# LCD_ControlRev1Fix1.net
KiCad netlist of a schematic drawn in EAGLE
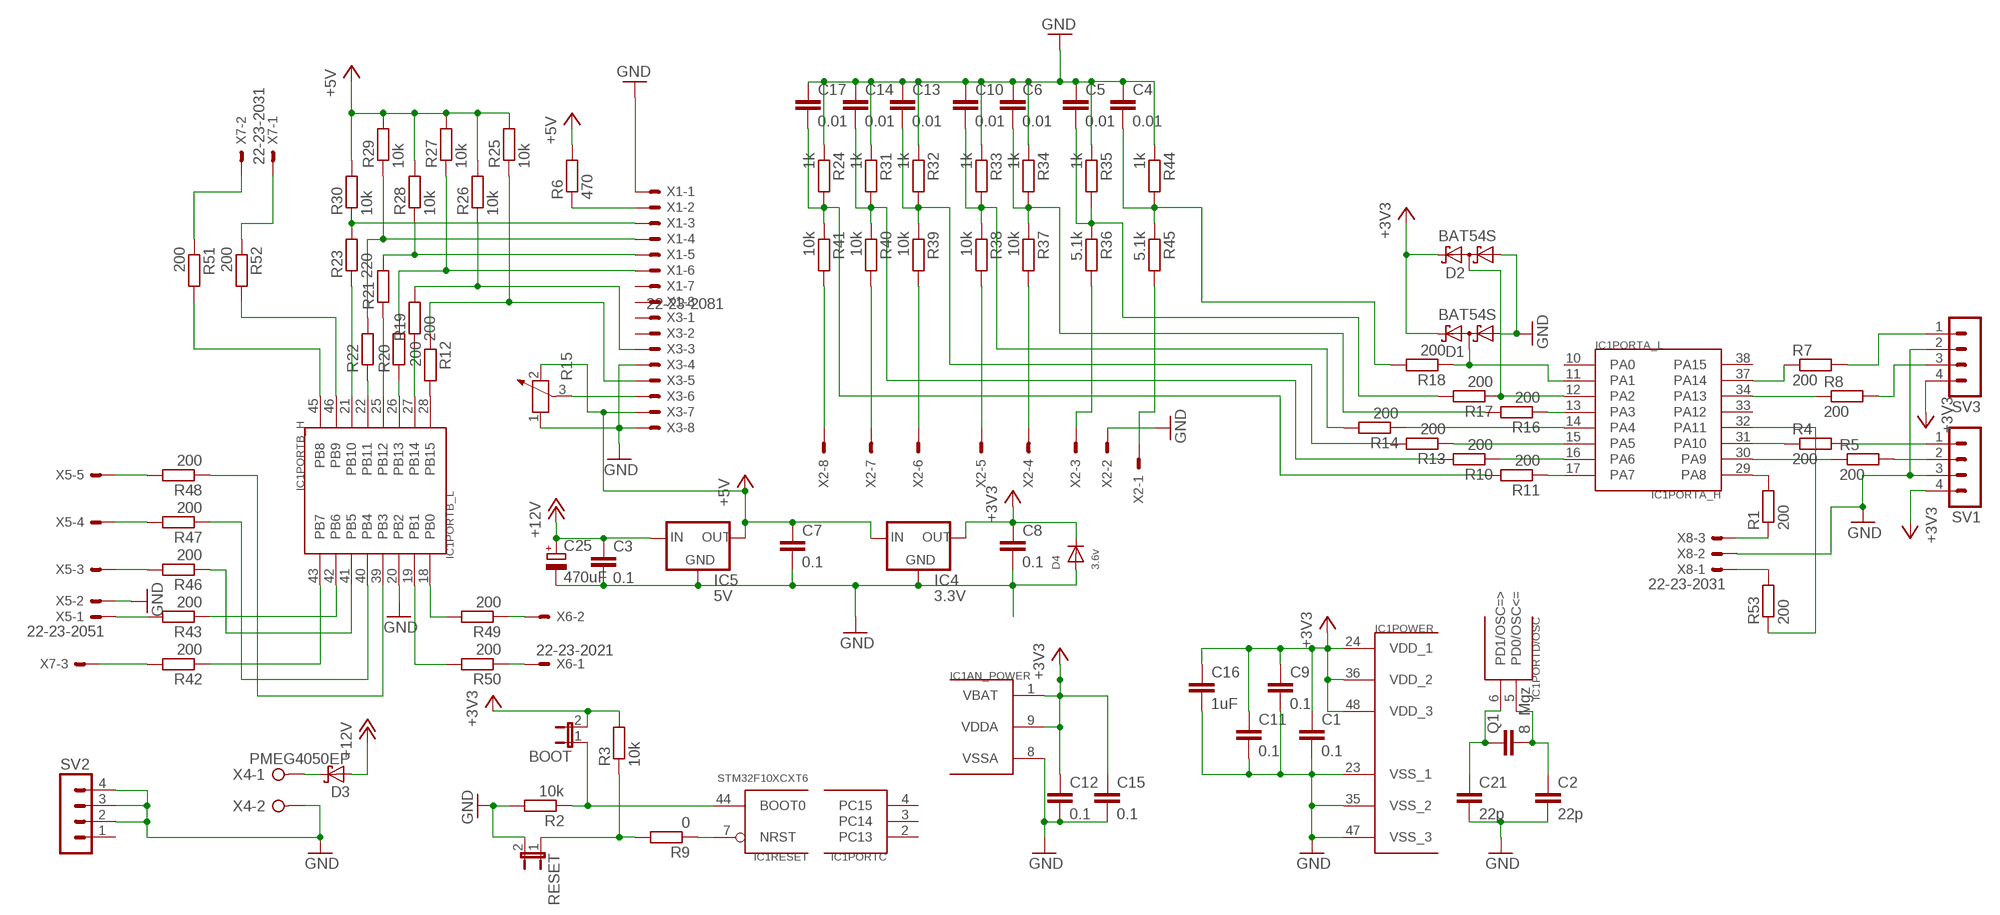
[diagram p0: schematic, sheet 1]

(export (version "E")
  (design (tool "Eeschema 10.0.6"))
  (components
    (comp (ref "BOOT")
      (value "JP1E")
      (footprint "eagle-import:JP1")
      (libsource (lib "eagle-import") (part "JP1E"))
    )
    (comp (ref "C1")
      (value "0.1")
      (footprint "eagle-import:C0402")
      (libsource (lib "eagle-import") (part "C-EUC0402"))
    )
    (comp (ref "C2")
      (value "22p")
      (footprint "eagle-import:C0603")
      (libsource (lib "eagle-import") (part "C-EUC0603"))
    )
    (comp (ref "C3")
      (value "0.1")
      (footprint "eagle-import:C1206")
      (libsource (lib "eagle-import") (part "C-EUC1206"))
    )
    (comp (ref "C4")
      (value "0.01")
      (footprint "eagle-import:C0603")
      (libsource (lib "eagle-import") (part "rcl_334_C-EUC0603"))
    )
    (comp (ref "C5")
      (value "0.01")
      (footprint "eagle-import:C0603")
      (libsource (lib "eagle-import") (part "rcl_334_C-EUC0603"))
    )
    (comp (ref "C6")
      (value "0.01")
      (footprint "eagle-import:C0603")
      (libsource (lib "eagle-import") (part "rcl_334_C-EUC0603"))
    )
    (comp (ref "C7")
      (value "0.1")
      (footprint "eagle-import:C1206")
      (libsource (lib "eagle-import") (part "C-EUC1206"))
    )
    (comp (ref "C8")
      (value "0.1")
      (footprint "eagle-import:C1206")
      (libsource (lib "eagle-import") (part "C-EUC1206"))
    )
    (comp (ref "C9")
      (value "0.1")
      (footprint "eagle-import:C0402")
      (libsource (lib "eagle-import") (part "C-EUC0402"))
    )
    (comp (ref "C10")
      (value "0.01")
      (footprint "eagle-import:C0603")
      (libsource (lib "eagle-import") (part "rcl_334_C-EUC0603"))
    )
    (comp (ref "C11")
      (value "0.1")
      (footprint "eagle-import:C0402")
      (libsource (lib "eagle-import") (part "C-EUC0402"))
    )
    (comp (ref "C12")
      (value "0.1")
      (footprint "eagle-import:C0402")
      (libsource (lib "eagle-import") (part "C-EUC0402"))
    )
    (comp (ref "C13")
      (value "0.01")
      (footprint "eagle-import:C0603")
      (libsource (lib "eagle-import") (part "rcl_334_C-EUC0603"))
    )
    (comp (ref "C14")
      (value "0.01")
      (footprint "eagle-import:C0603")
      (libsource (lib "eagle-import") (part "rcl_334_C-EUC0603"))
    )
    (comp (ref "C15")
      (value "0.1")
      (footprint "eagle-import:C0402")
      (libsource (lib "eagle-import") (part "C-EUC0402"))
    )
    (comp (ref "C16")
      (value "1uF")
      (footprint "eagle-import:C0603")
      (libsource (lib "eagle-import") (part "C-EUC0603"))
    )
    (comp (ref "C17")
      (value "0.01")
      (footprint "eagle-import:C0603")
      (libsource (lib "eagle-import") (part "rcl_334_C-EUC0603"))
    )
    (comp (ref "C21")
      (value "22p")
      (footprint "eagle-import:C0603")
      (libsource (lib "eagle-import") (part "C-EUC0603"))
    )
    (comp (ref "C25")
      (value "470uF")
      (footprint "eagle-import:E5-10,5")
      (libsource (lib "eagle-import") (part "CPOL-EUE5-10.5"))
    )
    (comp (ref "D1")
      (value "BAT54S")
      (footprint "eagle-import:SOT23")
      (libsource (lib "eagle-import") (part "BAT54S"))
    )
    (comp (ref "D2")
      (value "BAT54S")
      (footprint "eagle-import:SOT23")
      (libsource (lib "eagle-import") (part "BAT54S"))
    )
    (comp (ref "D3")
      (value "PMEG4050EP")
      (footprint "eagle-import:SOD128")
      (libsource (lib "eagle-import") (part "PMEG4050EP"))
    )
    (comp (ref "D4")
      (value "3.6v")
      (footprint "eagle-import:SOD-123")
      (libsource (lib "eagle-import") (part "DIODESOD-123"))
    )
    (comp (ref "IC1")
      (value "STM32F10XCXT6")
      (footprint "eagle-import:TQFP48")
      (libsource (lib "eagle-import") (part "STM32F10XCXT6"))
    )
    (comp (ref "IC4")
      (value "3.3V")
      (footprint "eagle-import:SOT223")
      (libsource (lib "eagle-import") (part "LM1117"))
    )
    (comp (ref "IC5")
      (value "5V")
      (footprint "eagle-import:SOT223")
      (libsource (lib "eagle-import") (part "LM1117"))
    )
    (comp (ref "Q1")
      (value "8 Mgz")
      (footprint "eagle-import:C050-024X044")
      (libsource (lib "eagle-import") (part "C-EU050-024X044"))
    )
    (comp (ref "R1")
      (value "200")
      (footprint "eagle-import:R0603")
      (libsource (lib "eagle-import") (part "R-EU_R0603"))
    )
    (comp (ref "R2")
      (value "10k")
      (footprint "eagle-import:R0603")
      (libsource (lib "eagle-import") (part "R-EU_R0603"))
    )
    (comp (ref "R3")
      (value "10k")
      (footprint "eagle-import:M1206")
      (libsource (lib "eagle-import") (part "R-EU_M1206"))
    )
    (comp (ref "R4")
      (value "200")
      (footprint "eagle-import:R0603")
      (libsource (lib "eagle-import") (part "R-EU_R0603"))
    )
    (comp (ref "R5")
      (value "200")
      (footprint "eagle-import:R0603")
      (libsource (lib "eagle-import") (part "R-EU_R0603"))
    )
    (comp (ref "R6")
      (value "470")
      (footprint "eagle-import:R0603")
      (libsource (lib "eagle-import") (part "R-EU_R0603"))
    )
    (comp (ref "R7")
      (value "200")
      (footprint "eagle-import:R0603")
      (libsource (lib "eagle-import") (part "R-EU_R0603"))
    )
    (comp (ref "R8")
      (value "200")
      (footprint "eagle-import:R0603")
      (libsource (lib "eagle-import") (part "R-EU_R0603"))
    )
    (comp (ref "R9")
      (value "0")
      (footprint "eagle-import:M1206")
      (libsource (lib "eagle-import") (part "R-EU_M1206"))
    )
    (comp (ref "R10")
      (value "200")
      (footprint "eagle-import:R0603")
      (libsource (lib "eagle-import") (part "R-EU_R0603"))
    )
    (comp (ref "R11")
      (value "200")
      (footprint "eagle-import:R0603")
      (libsource (lib "eagle-import") (part "R-EU_R0603"))
    )
    (comp (ref "R12")
      (value "200")
      (footprint "eagle-import:M1206")
      (libsource (lib "eagle-import") (part "R-EU_M1206"))
    )
    (comp (ref "R13")
      (value "200")
      (footprint "eagle-import:R0603")
      (libsource (lib "eagle-import") (part "R-EU_R0603"))
    )
    (comp (ref "R14")
      (value "200")
      (footprint "eagle-import:R0603")
      (libsource (lib "eagle-import") (part "R-EU_R0603"))
    )
    (comp (ref "R15")
      (value "POTENTIOMETER_PT-10S")
      (footprint "eagle-import:PT-10S")
      (libsource (lib "eagle-import") (part "POTENTIOMETER_PT-10S"))
    )
    (comp (ref "R16")
      (value "200")
      (footprint "eagle-import:R0603")
      (libsource (lib "eagle-import") (part "R-EU_R0603"))
    )
    (comp (ref "R17")
      (value "200")
      (footprint "eagle-import:R0603")
      (libsource (lib "eagle-import") (part "R-EU_R0603"))
    )
    (comp (ref "R18")
      (value "200")
      (footprint "eagle-import:R0603")
      (libsource (lib "eagle-import") (part "R-EU_R0603"))
    )
    (comp (ref "R19")
      (value "200")
      (footprint "eagle-import:R0603")
      (libsource (lib "eagle-import") (part "R-EU_R0603"))
    )
    (comp (ref "R20")
      (value "R-EU_R0603")
      (footprint "eagle-import:R0603")
      (libsource (lib "eagle-import") (part "R-EU_R0603"))
    )
    (comp (ref "R21")
      (value "R-EU_R0603")
      (footprint "eagle-import:R0603")
      (libsource (lib "eagle-import") (part "R-EU_R0603"))
    )
    (comp (ref "R22")
      (value "R-EU_R0603")
      (footprint "eagle-import:R0603")
      (libsource (lib "eagle-import") (part "R-EU_R0603"))
    )
    (comp (ref "R23")
      (value "220")
      (footprint "eagle-import:R0603")
      (libsource (lib "eagle-import") (part "R-EU_R0603"))
    )
    (comp (ref "R24")
      (value "1k")
      (footprint "eagle-import:R0603")
      (libsource (lib "eagle-import") (part "R-EU_R0603"))
    )
    (comp (ref "R25")
      (value "10k")
      (footprint "eagle-import:R0603")
      (libsource (lib "eagle-import") (part "R-EU_R0603"))
    )
    (comp (ref "R26")
      (value "10k")
      (footprint "eagle-import:R0603")
      (libsource (lib "eagle-import") (part "R-EU_R0603"))
    )
    (comp (ref "R27")
      (value "10k")
      (footprint "eagle-import:R0603")
      (libsource (lib "eagle-import") (part "R-EU_R0603"))
    )
    (comp (ref "R28")
      (value "10k")
      (footprint "eagle-import:R0603")
      (libsource (lib "eagle-import") (part "R-EU_R0603"))
    )
    (comp (ref "R29")
      (value "10k")
      (footprint "eagle-import:R0603")
      (libsource (lib "eagle-import") (part "R-EU_R0603"))
    )
    (comp (ref "R30")
      (value "10k")
      (footprint "eagle-import:R0603")
      (libsource (lib "eagle-import") (part "R-EU_R0603"))
    )
    (comp (ref "R31")
      (value "1k")
      (footprint "eagle-import:R0603")
      (libsource (lib "eagle-import") (part "R-EU_R0603"))
    )
    (comp (ref "R32")
      (value "1k")
      (footprint "eagle-import:R0603")
      (libsource (lib "eagle-import") (part "R-EU_R0603"))
    )
    (comp (ref "R33")
      (value "1k")
      (footprint "eagle-import:R0603")
      (libsource (lib "eagle-import") (part "R-EU_R0603"))
    )
    (comp (ref "R34")
      (value "1k")
      (footprint "eagle-import:R0603")
      (libsource (lib "eagle-import") (part "R-EU_R0603"))
    )
    (comp (ref "R35")
      (value "1k")
      (footprint "eagle-import:R0603")
      (fields (field (name "SPICEPREFIX") "R"))
      (libsource (lib "eagle-import") (part "R-EU_R0603"))
    )
    (comp (ref "R36")
      (value "5.1k")
      (footprint "eagle-import:R0603")
      (libsource (lib "eagle-import") (part "R-EU_R0603"))
    )
    (comp (ref "R37")
      (value "10k")
      (footprint "eagle-import:R0603")
      (libsource (lib "eagle-import") (part "R-EU_R0603"))
    )
    (comp (ref "R38")
      (value "10k")
      (footprint "eagle-import:R0603")
      (libsource (lib "eagle-import") (part "R-EU_R0603"))
    )
    (comp (ref "R39")
      (value "10k")
      (footprint "eagle-import:R0603")
      (libsource (lib "eagle-import") (part "R-EU_R0603"))
    )
    (comp (ref "R40")
      (value "10k")
      (footprint "eagle-import:R0603")
      (libsource (lib "eagle-import") (part "R-EU_R0603"))
    )
    (comp (ref "R41")
      (value "10k")
      (footprint "eagle-import:R0603")
      (libsource (lib "eagle-import") (part "R-EU_R0603"))
    )
    (comp (ref "R42")
      (value "200")
      (footprint "eagle-import:R0603")
      (libsource (lib "eagle-import") (part "R-EU_R0603"))
    )
    (comp (ref "R43")
      (value "200")
      (footprint "eagle-import:R0603")
      (libsource (lib "eagle-import") (part "R-EU_R0603"))
    )
    (comp (ref "R44")
      (value "1k")
      (footprint "eagle-import:R0603")
      (libsource (lib "eagle-import") (part "R-EU_R0603"))
    )
    (comp (ref "R45")
      (value "5.1k")
      (footprint "eagle-import:R0603")
      (libsource (lib "eagle-import") (part "R-EU_R0603"))
    )
    (comp (ref "R46")
      (value "200")
      (footprint "eagle-import:R0603")
      (libsource (lib "eagle-import") (part "R-EU_R0603"))
    )
    (comp (ref "R47")
      (value "200")
      (footprint "eagle-import:R0603")
      (libsource (lib "eagle-import") (part "R-EU_R0603"))
    )
    (comp (ref "R48")
      (value "200")
      (footprint "eagle-import:R0603")
      (libsource (lib "eagle-import") (part "R-EU_R0603"))
    )
    (comp (ref "R49")
      (value "200")
      (footprint "eagle-import:R0603")
      (libsource (lib "eagle-import") (part "R-EU_R0603"))
    )
    (comp (ref "R50")
      (value "200")
      (footprint "eagle-import:R0603")
      (libsource (lib "eagle-import") (part "R-EU_R0603"))
    )
    (comp (ref "R51")
      (value "200")
      (footprint "eagle-import:R0603")
      (libsource (lib "eagle-import") (part "R-EU_R0603"))
    )
    (comp (ref "R52")
      (value "200")
      (footprint "eagle-import:R0603")
      (libsource (lib "eagle-import") (part "R-EU_R0603"))
    )
    (comp (ref "R53")
      (value "200")
      (footprint "eagle-import:R0603")
      (libsource (lib "eagle-import") (part "R-EU_R0603"))
    )
    (comp (ref "RESET")
      (value "JP1E")
      (footprint "eagle-import:JP1")
      (libsource (lib "eagle-import") (part "JP1E"))
    )
    (comp (ref "SV1")
      (value "MA04-1")
      (footprint "eagle-import:MA04-1")
      (libsource (lib "eagle-import") (part "MA04-1"))
    )
    (comp (ref "SV2")
      (value "MA04-1")
      (footprint "eagle-import:MA04-1")
      (libsource (lib "eagle-import") (part "MA04-1"))
    )
    (comp (ref "SV3")
      (value "MA04-1")
      (footprint "eagle-import:MA04-1")
      (libsource (lib "eagle-import") (part "MA04-1"))
    )
    (comp (ref "X1")
      (value "22-23-2081")
      (footprint "eagle-import:22-23-2081")
      (fields (field (name "MF") "MOLEX"))
      (libsource (lib "eagle-import") (part "22-23-2081"))
    )
    (comp (ref "X2")
      (value "22-23-2081")
      (footprint "eagle-import:22-23-2081")
      (fields (field (name "MF") "MOLEX"))
      (libsource (lib "eagle-import") (part "con-molex_165_22-23-2081"))
    )
    (comp (ref "X3")
      (value "22-23-2081")
      (footprint "eagle-import:22-23-2081")
      (fields (field (name "MF") "MOLEX"))
      (libsource (lib "eagle-import") (part "22-23-2081"))
    )
    (comp (ref "X4")
      (value "W237-02P")
      (footprint "eagle-import:W237-132")
      (libsource (lib "eagle-import") (part "W237-02P"))
    )
    (comp (ref "X5")
      (value "22-23-2051")
      (footprint "eagle-import:22-23-2051")
      (fields (field (name "MF") "MOLEX"))
      (libsource (lib "eagle-import") (part "22-23-2051"))
    )
    (comp (ref "X6")
      (value "22-23-2021")
      (footprint "eagle-import:22-23-2021")
      (fields (field (name "MF") "MOLEX"))
      (libsource (lib "eagle-import") (part "22-23-2021"))
    )
    (comp (ref "X7")
      (value "22-23-2031")
      (footprint "eagle-import:22-23-2031")
      (fields (field (name "MF") "MOLEX"))
      (libsource (lib "eagle-import") (part "22-23-2031"))
    )
    (comp (ref "X8")
      (value "22-23-2031")
      (footprint "eagle-import:22-23-2031")
      (fields (field (name "MF") "MOLEX"))
      (libsource (lib "eagle-import") (part "22-23-2031"))
    )
  )
  (nets
    (net (code "1") (name "+3V3") (class "Default")
      (node (ref "BOOT") (pin "2") (pinfunction "2_2") (pintype "passive"))
      (node (ref "C1") (pin "1") (pinfunction "1_1") (pintype "passive"))
      (node (ref "C11") (pin "1") (pinfunction "1_1") (pintype "passive"))
      (node (ref "C12") (pin "1") (pinfunction "1_1") (pintype "passive"))
      (node (ref "C15") (pin "1") (pinfunction "1_1") (pintype "passive"))
      (node (ref "C16") (pin "1") (pinfunction "1_1") (pintype "passive"))
      (node (ref "C8") (pin "1") (pinfunction "1_1") (pintype "passive"))
      (node (ref "C9") (pin "1") (pinfunction "1_1") (pintype "passive"))
      (node (ref "D1") (pin "2") (pinfunction "C2_2") (pintype "passive"))
      (node (ref "D2") (pin "2") (pinfunction "C2_2") (pintype "passive"))
      (node (ref "D4") (pin "C") (pinfunction "C_C") (pintype "passive"))
      (node (ref "IC1") (pin "1") (pinfunction "VBAT_1") (pintype "power_in"))
      (node (ref "IC1") (pin "24") (pinfunction "VDD_1_24") (pintype "power_in"))
      (node (ref "IC1") (pin "36") (pinfunction "VDD_2_36") (pintype "power_in"))
      (node (ref "IC1") (pin "48") (pinfunction "VDD_3_48") (pintype "power_in"))
      (node (ref "IC1") (pin "9") (pinfunction "VDDA_9") (pintype "power_in"))
      (node (ref "IC4") (pin "2") (pinfunction "OUT_2") (pintype "passive"))
      (node (ref "IC4") (pin "4") (pinfunction "OUT_4") (pintype "passive"))
      (node (ref "R3") (pin "2") (pinfunction "2_2") (pintype "passive"))
      (node (ref "SV1") (pin "4") (pinfunction "4_4") (pintype "passive"))
      (node (ref "SV3") (pin "4") (pinfunction "4_4") (pintype "passive"))
    )
    (net (code "2") (name "+5V") (class "Default")
      (node (ref "C7") (pin "1") (pinfunction "1_1") (pintype "passive"))
      (node (ref "IC4") (pin "3") (pinfunction "IN_3") (pintype "input"))
      (node (ref "IC5") (pin "2") (pinfunction "OUT_2") (pintype "passive"))
      (node (ref "IC5") (pin "4") (pinfunction "OUT_4") (pintype "passive"))
      (node (ref "R15") (pin "2") (pinfunction "2_2") (pintype "passive"))
      (node (ref "R25") (pin "2") (pinfunction "2_2") (pintype "passive"))
      (node (ref "R26") (pin "2") (pinfunction "2_2") (pintype "passive"))
      (node (ref "R27") (pin "2") (pinfunction "2_2") (pintype "passive"))
      (node (ref "R28") (pin "2") (pinfunction "2_2") (pintype "passive"))
      (node (ref "R29") (pin "2") (pinfunction "2_2") (pintype "passive"))
      (node (ref "R30") (pin "2") (pinfunction "2_2") (pintype "passive"))
      (node (ref "R6") (pin "2") (pinfunction "2_2") (pintype "passive"))
      (node (ref "X3") (pin "7") (pinfunction "S_7") (pintype "passive"))
    )
    (net (code "3") (name "+12V") (class "Default")
      (node (ref "C25") (pin "+") (pinfunction "+_+") (pintype "passive"))
      (node (ref "C3") (pin "1") (pinfunction "1_1") (pintype "passive"))
      (node (ref "D3") (pin "2") (pinfunction "A_2") (pintype "passive"))
      (node (ref "IC5") (pin "3") (pinfunction "IN_3") (pintype "input"))
    )
    (net (code "4") (name "GND") (class "Default")
      (node (ref "C1") (pin "2") (pinfunction "2_2") (pintype "passive"))
      (node (ref "C10") (pin "1") (pinfunction "1_1") (pintype "passive"))
      (node (ref "C11") (pin "2") (pinfunction "2_2") (pintype "passive"))
      (node (ref "C12") (pin "2") (pinfunction "2_2") (pintype "passive"))
      (node (ref "C13") (pin "1") (pinfunction "1_1") (pintype "passive"))
      (node (ref "C14") (pin "1") (pinfunction "1_1") (pintype "passive"))
      (node (ref "C15") (pin "2") (pinfunction "2_2") (pintype "passive"))
      (node (ref "C16") (pin "2") (pinfunction "2_2") (pintype "passive"))
      (node (ref "C17") (pin "1") (pinfunction "1_1") (pintype "passive"))
      (node (ref "C2") (pin "2") (pinfunction "2_2") (pintype "passive"))
      (node (ref "C21") (pin "2") (pinfunction "2_2") (pintype "passive"))
      (node (ref "C25") (pin "-") (pinfunction "-_-") (pintype "passive"))
      (node (ref "C3") (pin "2") (pinfunction "2_2") (pintype "passive"))
      (node (ref "C4") (pin "1") (pinfunction "1_1") (pintype "passive"))
      (node (ref "C5") (pin "1") (pinfunction "1_1") (pintype "passive"))
      (node (ref "C6") (pin "1") (pinfunction "1_1") (pintype "passive"))
      (node (ref "C7") (pin "2") (pinfunction "2_2") (pintype "passive"))
      (node (ref "C8") (pin "2") (pinfunction "2_2") (pintype "passive"))
      (node (ref "C9") (pin "2") (pinfunction "2_2") (pintype "passive"))
      (node (ref "D1") (pin "1") (pinfunction "A1_1") (pintype "passive"))
      (node (ref "D2") (pin "1") (pinfunction "A1_1") (pintype "passive"))
      (node (ref "D4") (pin "A") (pinfunction "A_A") (pintype "passive"))
      (node (ref "IC1") (pin "20") (pinfunction "PB2_20") (pintype "bidirectional"))
      (node (ref "IC1") (pin "23") (pinfunction "VSS_1_23") (pintype "power_in"))
      (node (ref "IC1") (pin "35") (pinfunction "VSS_2_35") (pintype "power_in"))
      (node (ref "IC1") (pin "47") (pinfunction "VSS_3_47") (pintype "power_in"))
      (node (ref "IC1") (pin "8") (pinfunction "VSSA_8") (pintype "power_in"))
      (node (ref "IC4") (pin "1") (pinfunction "GND_1") (pintype "input"))
      (node (ref "IC5") (pin "1") (pinfunction "GND_1") (pintype "input"))
      (node (ref "R15") (pin "1") (pinfunction "1_1") (pintype "passive"))
      (node (ref "R2") (pin "2") (pinfunction "2_2") (pintype "passive"))
      (node (ref "R24") (pin "1") (pinfunction "1_1") (pintype "passive"))
      (node (ref "R31") (pin "1") (pinfunction "1_1") (pintype "passive"))
      (node (ref "R32") (pin "1") (pinfunction "1_1") (pintype "passive"))
      (node (ref "R33") (pin "1") (pinfunction "1_1") (pintype "passive"))
      (node (ref "R34") (pin "1") (pinfunction "1_1") (pintype "passive"))
      (node (ref "R35") (pin "1") (pinfunction "1_1") (pintype "passive"))
      (node (ref "R44") (pin "1") (pinfunction "1_1") (pintype "passive"))
      (node (ref "RESET") (pin "2") (pinfunction "2_2") (pintype "passive"))
      (node (ref "SV1") (pin "3") (pinfunction "3_3") (pintype "passive"))
      (node (ref "SV2") (pin "2") (pinfunction "2_2") (pintype "passive"))
      (node (ref "SV2") (pin "3") (pinfunction "3_3") (pintype "passive"))
      (node (ref "SV2") (pin "4") (pinfunction "4_4") (pintype "passive"))
      (node (ref "SV3") (pin "2") (pinfunction "2_2") (pintype "passive"))
      (node (ref "X1") (pin "1") (pinfunction "S_1") (pintype "passive"))
      (node (ref "X2") (pin "2") (pinfunction "S_2") (pintype "passive"))
      (node (ref "X3") (pin "4") (pinfunction "S_4") (pintype "passive"))
      (node (ref "X3") (pin "8") (pinfunction "S_8") (pintype "passive"))
      (node (ref "X4") (pin "2") (pinfunction "KL_2") (pintype "passive"))
      (node (ref "X5") (pin "2") (pinfunction "S_2") (pintype "passive"))
      (node (ref "X8") (pin "2") (pinfunction "S_2") (pintype "passive"))
    )
    (net (code "5") (name "Net-(C4-Pad2)") (class "Default")
      (node (ref "C4") (pin "2") (pinfunction "2_2") (pintype "passive"))
      (node (ref "R18") (pin "2") (pinfunction "2_2") (pintype "passive"))
      (node (ref "R44") (pin "2") (pinfunction "2_2") (pintype "passive"))
      (node (ref "R45") (pin "1") (pinfunction "1_1") (pintype "passive"))
    )
    (net (code "6") (name "Net-(C5-Pad2)") (class "Default")
      (node (ref "C5") (pin "2") (pinfunction "2_2") (pintype "passive"))
      (node (ref "R17") (pin "2") (pinfunction "2_2") (pintype "passive"))
      (node (ref "R35") (pin "2") (pinfunction "2_2") (pintype "passive"))
      (node (ref "R36") (pin "1") (pinfunction "1_1") (pintype "passive"))
    )
    (net (code "7") (name "Net-(C6-Pad2)") (class "Default")
      (node (ref "C6") (pin "2") (pinfunction "2_2") (pintype "passive"))
      (node (ref "R16") (pin "2") (pinfunction "2_2") (pintype "passive"))
      (node (ref "R34") (pin "2") (pinfunction "2_2") (pintype "passive"))
      (node (ref "R37") (pin "1") (pinfunction "1_1") (pintype "passive"))
    )
    (net (code "8") (name "Net-(C10-Pad2)") (class "Default")
      (node (ref "C10") (pin "2") (pinfunction "2_2") (pintype "passive"))
      (node (ref "R14") (pin "2") (pinfunction "2_2") (pintype "passive"))
      (node (ref "R33") (pin "2") (pinfunction "2_2") (pintype "passive"))
      (node (ref "R38") (pin "1") (pinfunction "1_1") (pintype "passive"))
    )
    (net (code "9") (name "Net-(C13-Pad2)") (class "Default")
      (node (ref "C13") (pin "2") (pinfunction "2_2") (pintype "passive"))
      (node (ref "R13") (pin "2") (pinfunction "2_2") (pintype "passive"))
      (node (ref "R32") (pin "2") (pinfunction "2_2") (pintype "passive"))
      (node (ref "R39") (pin "1") (pinfunction "1_1") (pintype "passive"))
    )
    (net (code "10") (name "Net-(C14-Pad2)") (class "Default")
      (node (ref "C14") (pin "2") (pinfunction "2_2") (pintype "passive"))
      (node (ref "R10") (pin "2") (pinfunction "2_2") (pintype "passive"))
      (node (ref "R31") (pin "2") (pinfunction "2_2") (pintype "passive"))
      (node (ref "R40") (pin "1") (pinfunction "1_1") (pintype "passive"))
    )
    (net (code "11") (name "Net-(C17-Pad2)") (class "Default")
      (node (ref "C17") (pin "2") (pinfunction "2_2") (pintype "passive"))
      (node (ref "R11") (pin "2") (pinfunction "2_2") (pintype "passive"))
      (node (ref "R24") (pin "2") (pinfunction "2_2") (pintype "passive"))
      (node (ref "R41") (pin "1") (pinfunction "1_1") (pintype "passive"))
    )
    (net (code "12") (name "Net-(D1-C1A2)") (class "Default")
      (node (ref "D1") (pin "3") (pinfunction "C1A2_3") (pintype "passive"))
      (node (ref "IC1") (pin "11") (pinfunction "PA1_11") (pintype "bidirectional"))
      (node (ref "R18") (pin "1") (pinfunction "1_1") (pintype "passive"))
    )
    (net (code "13") (name "Net-(D2-C1A2)") (class "Default")
      (node (ref "D2") (pin "3") (pinfunction "C1A2_3") (pintype "passive"))
      (node (ref "IC1") (pin "12") (pinfunction "PA2_12") (pintype "bidirectional"))
      (node (ref "R17") (pin "1") (pinfunction "1_1") (pintype "passive"))
    )
    (net (code "14") (name "Net-(D3-K)") (class "Default")
      (node (ref "D3") (pin "1") (pinfunction "K_1") (pintype "passive"))
      (node (ref "X4") (pin "1") (pinfunction "KL_1") (pintype "passive"))
    )
    (net (code "15") (name "Net-(IC1B-PA8)") (class "Default")
      (node (ref "IC1") (pin "29") (pinfunction "PA8_29") (pintype "bidirectional"))
      (node (ref "R1") (pin "2") (pinfunction "2_2") (pintype "passive"))
    )
    (net (code "16") (name "Net-(IC1B-PA9)") (class "Default")
      (node (ref "IC1") (pin "30") (pinfunction "PA9_30") (pintype "bidirectional"))
      (node (ref "R5") (pin "1") (pinfunction "1_1") (pintype "passive"))
    )
    (net (code "17") (name "Net-(IC1B-PA10)") (class "Default")
      (node (ref "IC1") (pin "31") (pinfunction "PA10_31") (pintype "bidirectional"))
      (node (ref "R4") (pin "1") (pinfunction "1_1") (pintype "passive"))
    )
    (net (code "18") (name "Net-(IC1B-PA11)") (class "Default")
      (node (ref "IC1") (pin "32") (pinfunction "PA11_32") (pintype "bidirectional"))
      (node (ref "R53") (pin "1") (pinfunction "1_1") (pintype "passive"))
    )
    (net (code "19") (name "Net-(IC1B-PA13)") (class "Default")
      (node (ref "IC1") (pin "34") (pinfunction "PA13_34") (pintype "bidirectional"))
      (node (ref "R8") (pin "1") (pinfunction "1_1") (pintype "passive"))
    )
    (net (code "20") (name "Net-(IC1B-PA14)") (class "Default")
      (node (ref "IC1") (pin "37") (pinfunction "PA14_37") (pintype "bidirectional"))
      (node (ref "R7") (pin "1") (pinfunction "1_1") (pintype "passive"))
    )
    (net (code "21") (name "Net-(IC1C-PA3)") (class "Default")
      (node (ref "IC1") (pin "13") (pinfunction "PA3_13") (pintype "bidirectional"))
      (node (ref "R16") (pin "1") (pinfunction "1_1") (pintype "passive"))
    )
    (net (code "22") (name "Net-(IC1C-PA4)") (class "Default")
      (node (ref "IC1") (pin "14") (pinfunction "PA4_14") (pintype "bidirectional"))
      (node (ref "R14") (pin "1") (pinfunction "1_1") (pintype "passive"))
    )
    (net (code "23") (name "Net-(IC1C-PA5)") (class "Default")
      (node (ref "IC1") (pin "15") (pinfunction "PA5_15") (pintype "bidirectional"))
      (node (ref "R13") (pin "1") (pinfunction "1_1") (pintype "passive"))
    )
    (net (code "24") (name "Net-(IC1C-PA6)") (class "Default")
      (node (ref "IC1") (pin "16") (pinfunction "PA6_16") (pintype "bidirectional"))
      (node (ref "R10") (pin "1") (pinfunction "1_1") (pintype "passive"))
    )
    (net (code "25") (name "Net-(IC1C-PA7)") (class "Default")
      (node (ref "IC1") (pin "17") (pinfunction "PA7_17") (pintype "bidirectional"))
      (node (ref "R11") (pin "1") (pinfunction "1_1") (pintype "passive"))
    )
    (net (code "26") (name "Net-(IC1D-PB8)") (class "Default")
      (node (ref "IC1") (pin "45") (pinfunction "PB8_45") (pintype "bidirectional"))
      (node (ref "R51") (pin "2") (pinfunction "2_2") (pintype "passive"))
    )
    (net (code "27") (name "Net-(IC1D-PB9)") (class "Default")
      (node (ref "IC1") (pin "46") (pinfunction "PB9_46") (pintype "bidirectional"))
      (node (ref "R52") (pin "2") (pinfunction "2_2") (pintype "passive"))
    )
    (net (code "28") (name "Net-(IC1D-PB10)") (class "Default")
      (node (ref "IC1") (pin "21") (pinfunction "PB10_21") (pintype "bidirectional"))
      (node (ref "R23") (pin "1") (pinfunction "1_1") (pintype "passive"))
    )
    (net (code "29") (name "Net-(IC1D-PB11)") (class "Default")
      (node (ref "IC1") (pin "22") (pinfunction "PB11_22") (pintype "bidirectional"))
      (node (ref "R22") (pin "1") (pinfunction "1_1") (pintype "passive"))
    )
    (net (code "30") (name "Net-(IC1D-PB12)") (class "Default")
      (node (ref "IC1") (pin "25") (pinfunction "PB12_25") (pintype "bidirectional"))
      (node (ref "R21") (pin "1") (pinfunction "1_1") (pintype "passive"))
    )
    (net (code "31") (name "Net-(IC1D-PB13)") (class "Default")
      (node (ref "IC1") (pin "26") (pinfunction "PB13_26") (pintype "bidirectional"))
      (node (ref "R20") (pin "1") (pinfunction "1_1") (pintype "passive"))
    )
    (net (code "32") (name "Net-(IC1D-PB14)") (class "Default")
      (node (ref "IC1") (pin "27") (pinfunction "PB14_27") (pintype "bidirectional"))
      (node (ref "R19") (pin "1") (pinfunction "1_1") (pintype "passive"))
    )
    (net (code "33") (name "Net-(IC1D-PB15)") (class "Default")
      (node (ref "IC1") (pin "28") (pinfunction "PB15_28") (pintype "bidirectional"))
      (node (ref "R12") (pin "2") (pinfunction "2_2") (pintype "passive"))
    )
    (net (code "34") (name "Net-(IC1E-PB0)") (class "Default")
      (node (ref "IC1") (pin "18") (pinfunction "PB0_18") (pintype "bidirectional"))
      (node (ref "R49") (pin "2") (pinfunction "2_2") (pintype "passive"))
    )
    (net (code "35") (name "Net-(IC1E-PB1)") (class "Default")
      (node (ref "IC1") (pin "19") (pinfunction "PB1_19") (pintype "bidirectional"))
      (node (ref "R50") (pin "2") (pinfunction "2_2") (pintype "passive"))
    )
    (net (code "36") (name "Net-(IC1E-PB3)") (class "Default")
      (node (ref "IC1") (pin "39") (pinfunction "PB3_39") (pintype "bidirectional"))
      (node (ref "R48") (pin "1") (pinfunction "1_1") (pintype "passive"))
    )
    (net (code "37") (name "Net-(IC1E-PB4)") (class "Default")
      (node (ref "IC1") (pin "40") (pinfunction "PB4_40") (pintype "bidirectional"))
      (node (ref "R47") (pin "1") (pinfunction "1_1") (pintype "passive"))
    )
    (net (code "38") (name "Net-(IC1E-PB5)") (class "Default")
      (node (ref "IC1") (pin "41") (pinfunction "PB5_41") (pintype "bidirectional"))
      (node (ref "R46") (pin "1") (pinfunction "1_1") (pintype "passive"))
    )
    (net (code "39") (name "Net-(IC1E-PB6)") (class "Default")
      (node (ref "IC1") (pin "42") (pinfunction "PB6_42") (pintype "bidirectional"))
      (node (ref "R43") (pin "1") (pinfunction "1_1") (pintype "passive"))
    )
    (net (code "40") (name "Net-(IC1E-PB7)") (class "Default")
      (node (ref "IC1") (pin "43") (pinfunction "PB7_43") (pintype "bidirectional"))
      (node (ref "R42") (pin "1") (pinfunction "1_1") (pintype "passive"))
    )
    (net (code "41") (name "Net-(IC1G-PD0{slash}OSC<=)") (class "Default")
      (node (ref "C2") (pin "1") (pinfunction "1_1") (pintype "passive"))
      (node (ref "IC1") (pin "5") (pinfunction "PD0/OSC<=_5") (pintype "bidirectional"))
      (node (ref "Q1") (pin "2") (pinfunction "2_2") (pintype "passive"))
    )
    (net (code "42") (name "Net-(IC1G-PD1{slash}OSC=>)") (class "Default")
      (node (ref "C21") (pin "1") (pinfunction "1_1") (pintype "passive"))
      (node (ref "IC1") (pin "6") (pinfunction "PD1/OSC=>_6") (pintype "bidirectional"))
      (node (ref "Q1") (pin "1") (pinfunction "1_1") (pintype "passive"))
    )
    (net (code "43") (name "Net-(IC1I-BOOT0)") (class "Default")
      (node (ref "BOOT") (pin "1") (pinfunction "1_1") (pintype "passive"))
      (node (ref "IC1") (pin "44") (pinfunction "BOOT0_44") (pintype "input"))
      (node (ref "R2") (pin "1") (pinfunction "1_1") (pintype "passive"))
    )
    (net (code "44") (name "Net-(IC1I-NRST)") (class "Default")
      (node (ref "IC1") (pin "7") (pinfunction "NRST_7") (pintype "input"))
      (node (ref "R9") (pin "1") (pinfunction "1_1") (pintype "passive"))
    )
    (net (code "45") (name "Net-(R3-Pad1)") (class "Default")
      (node (ref "R3") (pin "1") (pinfunction "1_1") (pintype "passive"))
      (node (ref "R9") (pin "2") (pinfunction "2_2") (pintype "passive"))
      (node (ref "RESET") (pin "1") (pinfunction "1_1") (pintype "passive"))
    )
    (net (code "46") (name "Net-(R4-Pad2)") (class "Default")
      (node (ref "R4") (pin "2") (pinfunction "2_2") (pintype "passive"))
      (node (ref "SV1") (pin "1") (pinfunction "1_1") (pintype "passive"))
    )
    (net (code "47") (name "Net-(R5-Pad2)") (class "Default")
      (node (ref "R5") (pin "2") (pinfunction "2_2") (pintype "passive"))
      (node (ref "SV1") (pin "2") (pinfunction "2_2") (pintype "passive"))
    )
    (net (code "48") (name "Net-(R7-Pad2)") (class "Default")
      (node (ref "R7") (pin "2") (pinfunction "2_2") (pintype "passive"))
      (node (ref "SV3") (pin "1") (pinfunction "1_1") (pintype "passive"))
    )
    (net (code "49") (name "Net-(R8-Pad2)") (class "Default")
      (node (ref "R8") (pin "2") (pinfunction "2_2") (pintype "passive"))
      (node (ref "SV3") (pin "3") (pinfunction "3_3") (pintype "passive"))
    )
    (net (code "50") (name "Net-(X1B-S)") (class "Default")
      (node (ref "R6") (pin "1") (pinfunction "1_1") (pintype "passive"))
      (node (ref "X1") (pin "2") (pinfunction "S_2") (pintype "passive"))
    )
    (net (code "51") (name "Net-(X1C-S)") (class "Default")
      (node (ref "R23") (pin "2") (pinfunction "2_2") (pintype "passive"))
      (node (ref "R30") (pin "1") (pinfunction "1_1") (pintype "passive"))
      (node (ref "X1") (pin "3") (pinfunction "S_3") (pintype "passive"))
    )
    (net (code "52") (name "Net-(X1D-S)") (class "Default")
      (node (ref "R22") (pin "2") (pinfunction "2_2") (pintype "passive"))
      (node (ref "R29") (pin "1") (pinfunction "1_1") (pintype "passive"))
      (node (ref "X1") (pin "4") (pinfunction "S_4") (pintype "passive"))
    )
    (net (code "53") (name "Net-(X1E-S)") (class "Default")
      (node (ref "R21") (pin "2") (pinfunction "2_2") (pintype "passive"))
      (node (ref "R28") (pin "1") (pinfunction "1_1") (pintype "passive"))
      (node (ref "X1") (pin "5") (pinfunction "S_5") (pintype "passive"))
    )
    (net (code "54") (name "Net-(X1F-S)") (class "Default")
      (node (ref "R20") (pin "2") (pinfunction "2_2") (pintype "passive"))
      (node (ref "R27") (pin "1") (pinfunction "1_1") (pintype "passive"))
      (node (ref "X1") (pin "6") (pinfunction "S_6") (pintype "passive"))
    )
    (net (code "55") (name "Net-(X2A-S)") (class "Default")
      (node (ref "R45") (pin "2") (pinfunction "2_2") (pintype "passive"))
      (node (ref "X2") (pin "1") (pinfunction "S_1") (pintype "passive"))
    )
    (net (code "56") (name "Net-(X2C-S)") (class "Default")
      (node (ref "R36") (pin "2") (pinfunction "2_2") (pintype "passive"))
      (node (ref "X2") (pin "3") (pinfunction "S_3") (pintype "passive"))
    )
    (net (code "57") (name "Net-(X2D-S)") (class "Default")
      (node (ref "R37") (pin "2") (pinfunction "2_2") (pintype "passive"))
      (node (ref "X2") (pin "4") (pinfunction "S_4") (pintype "passive"))
    )
    (net (code "58") (name "Net-(X2E-S)") (class "Default")
      (node (ref "R38") (pin "2") (pinfunction "2_2") (pintype "passive"))
      (node (ref "X2") (pin "5") (pinfunction "S_5") (pintype "passive"))
    )
    (net (code "59") (name "Net-(X2F-S)") (class "Default")
      (node (ref "R39") (pin "2") (pinfunction "2_2") (pintype "passive"))
      (node (ref "X2") (pin "6") (pinfunction "S_6") (pintype "passive"))
    )
    (net (code "60") (name "Net-(X2G-S)") (class "Default")
      (node (ref "R40") (pin "2") (pinfunction "2_2") (pintype "passive"))
      (node (ref "X2") (pin "7") (pinfunction "S_7") (pintype "passive"))
    )
    (net (code "61") (name "Net-(X2H-S)") (class "Default")
      (node (ref "R41") (pin "2") (pinfunction "2_2") (pintype "passive"))
      (node (ref "X2") (pin "8") (pinfunction "S_8") (pintype "passive"))
    )
    (net (code "62") (name "Net-(X3C-S)") (class "Default")
      (node (ref "R19") (pin "2") (pinfunction "2_2") (pintype "passive"))
      (node (ref "R26") (pin "1") (pinfunction "1_1") (pintype "passive"))
      (node (ref "X3") (pin "3") (pinfunction "S_3") (pintype "passive"))
    )
    (net (code "63") (name "Net-(X3E-S)") (class "Default")
      (node (ref "R12") (pin "1") (pinfunction "1_1") (pintype "passive"))
      (node (ref "R25") (pin "1") (pinfunction "1_1") (pintype "passive"))
      (node (ref "X3") (pin "5") (pinfunction "S_5") (pintype "passive"))
    )
    (net (code "64") (name "Net-(X3F-S)") (class "Default")
      (node (ref "R15") (pin "3") (pinfunction "3_3") (pintype "passive"))
      (node (ref "X3") (pin "6") (pinfunction "S_6") (pintype "passive"))
    )
    (net (code "65") (name "Net-(X5A-S)") (class "Default")
      (node (ref "R43") (pin "2") (pinfunction "2_2") (pintype "passive"))
      (node (ref "X5") (pin "1") (pinfunction "S_1") (pintype "passive"))
    )
    (net (code "66") (name "Net-(X5C-S)") (class "Default")
      (node (ref "R46") (pin "2") (pinfunction "2_2") (pintype "passive"))
      (node (ref "X5") (pin "3") (pinfunction "S_3") (pintype "passive"))
    )
    (net (code "67") (name "Net-(X5D-S)") (class "Default")
      (node (ref "R47") (pin "2") (pinfunction "2_2") (pintype "passive"))
      (node (ref "X5") (pin "4") (pinfunction "S_4") (pintype "passive"))
    )
    (net (code "68") (name "Net-(X5E-S)") (class "Default")
      (node (ref "R48") (pin "2") (pinfunction "2_2") (pintype "passive"))
      (node (ref "X5") (pin "5") (pinfunction "S_5") (pintype "passive"))
    )
    (net (code "69") (name "Net-(X6A-S)") (class "Default")
      (node (ref "R50") (pin "1") (pinfunction "1_1") (pintype "passive"))
      (node (ref "X6") (pin "1") (pinfunction "S_1") (pintype "passive"))
    )
    (net (code "70") (name "Net-(X6B-S)") (class "Default")
      (node (ref "R49") (pin "1") (pinfunction "1_1") (pintype "passive"))
      (node (ref "X6") (pin "2") (pinfunction "S_2") (pintype "passive"))
    )
    (net (code "71") (name "Net-(X7A-S)") (class "Default")
      (node (ref "R52") (pin "1") (pinfunction "1_1") (pintype "passive"))
      (node (ref "X7") (pin "1") (pinfunction "S_1") (pintype "passive"))
    )
    (net (code "72") (name "Net-(X7B-S)") (class "Default")
      (node (ref "R51") (pin "1") (pinfunction "1_1") (pintype "passive"))
      (node (ref "X7") (pin "2") (pinfunction "S_2") (pintype "passive"))
    )
    (net (code "73") (name "Net-(X7C-S)") (class "Default")
      (node (ref "R42") (pin "2") (pinfunction "2_2") (pintype "passive"))
      (node (ref "X7") (pin "3") (pinfunction "S_3") (pintype "passive"))
    )
    (net (code "74") (name "Net-(X8A-S)") (class "Default")
      (node (ref "R53") (pin "2") (pinfunction "2_2") (pintype "passive"))
      (node (ref "X8") (pin "1") (pinfunction "S_1") (pintype "passive"))
    )
    (net (code "75") (name "Net-(X8C-S)") (class "Default")
      (node (ref "R1") (pin "1") (pinfunction "1_1") (pintype "passive"))
      (node (ref "X8") (pin "3") (pinfunction "S_3") (pintype "passive"))
    )
    (net (code "76") (name "unconnected-(IC1B-PA12-Pad33)") (class "Default")
      (node (ref "IC1") (pin "33") (pinfunction "PA12_33") (pintype "bidirectional"))
    )
    (net (code "77") (name "unconnected-(IC1B-PA15-Pad38)") (class "Default")
      (node (ref "IC1") (pin "38") (pinfunction "PA15_38") (pintype "bidirectional"))
    )
    (net (code "78") (name "unconnected-(IC1C-PA0-Pad10)") (class "Default")
      (node (ref "IC1") (pin "10") (pinfunction "PA0_10") (pintype "bidirectional"))
    )
    (net (code "79") (name "unconnected-(IC1F-PC13-Pad2)") (class "Default")
      (node (ref "IC1") (pin "2") (pinfunction "PC13_2") (pintype "bidirectional"))
    )
    (net (code "80") (name "unconnected-(IC1F-PC14-Pad3)") (class "Default")
      (node (ref "IC1") (pin "3") (pinfunction "PC14_3") (pintype "bidirectional"))
    )
    (net (code "81") (name "unconnected-(IC1F-PC15-Pad4)") (class "Default")
      (node (ref "IC1") (pin "4") (pinfunction "PC15_4") (pintype "bidirectional"))
    )
    (net (code "82") (name "unconnected-(SV2-Pad1)") (class "Default")
      (node (ref "SV2") (pin "1") (pinfunction "1_1") (pintype "passive"))
    )
    (net (code "83") (name "unconnected-(X1G-S-Pad7)") (class "Default")
      (node (ref "X1") (pin "7") (pinfunction "S_7") (pintype "passive"))
    )
    (net (code "84") (name "unconnected-(X1H-S-Pad8)") (class "Default")
      (node (ref "X1") (pin "8") (pinfunction "S_8") (pintype "passive"))
    )
    (net (code "85") (name "unconnected-(X3A-S-Pad1)") (class "Default")
      (node (ref "X3") (pin "1") (pinfunction "S_1") (pintype "passive"))
    )
    (net (code "86") (name "unconnected-(X3B-S-Pad2)") (class "Default")
      (node (ref "X3") (pin "2") (pinfunction "S_2") (pintype "passive"))
    )
  )
)
